# ZombieDelay.net
KiCad netlist of a schematic drawn in EAGLE
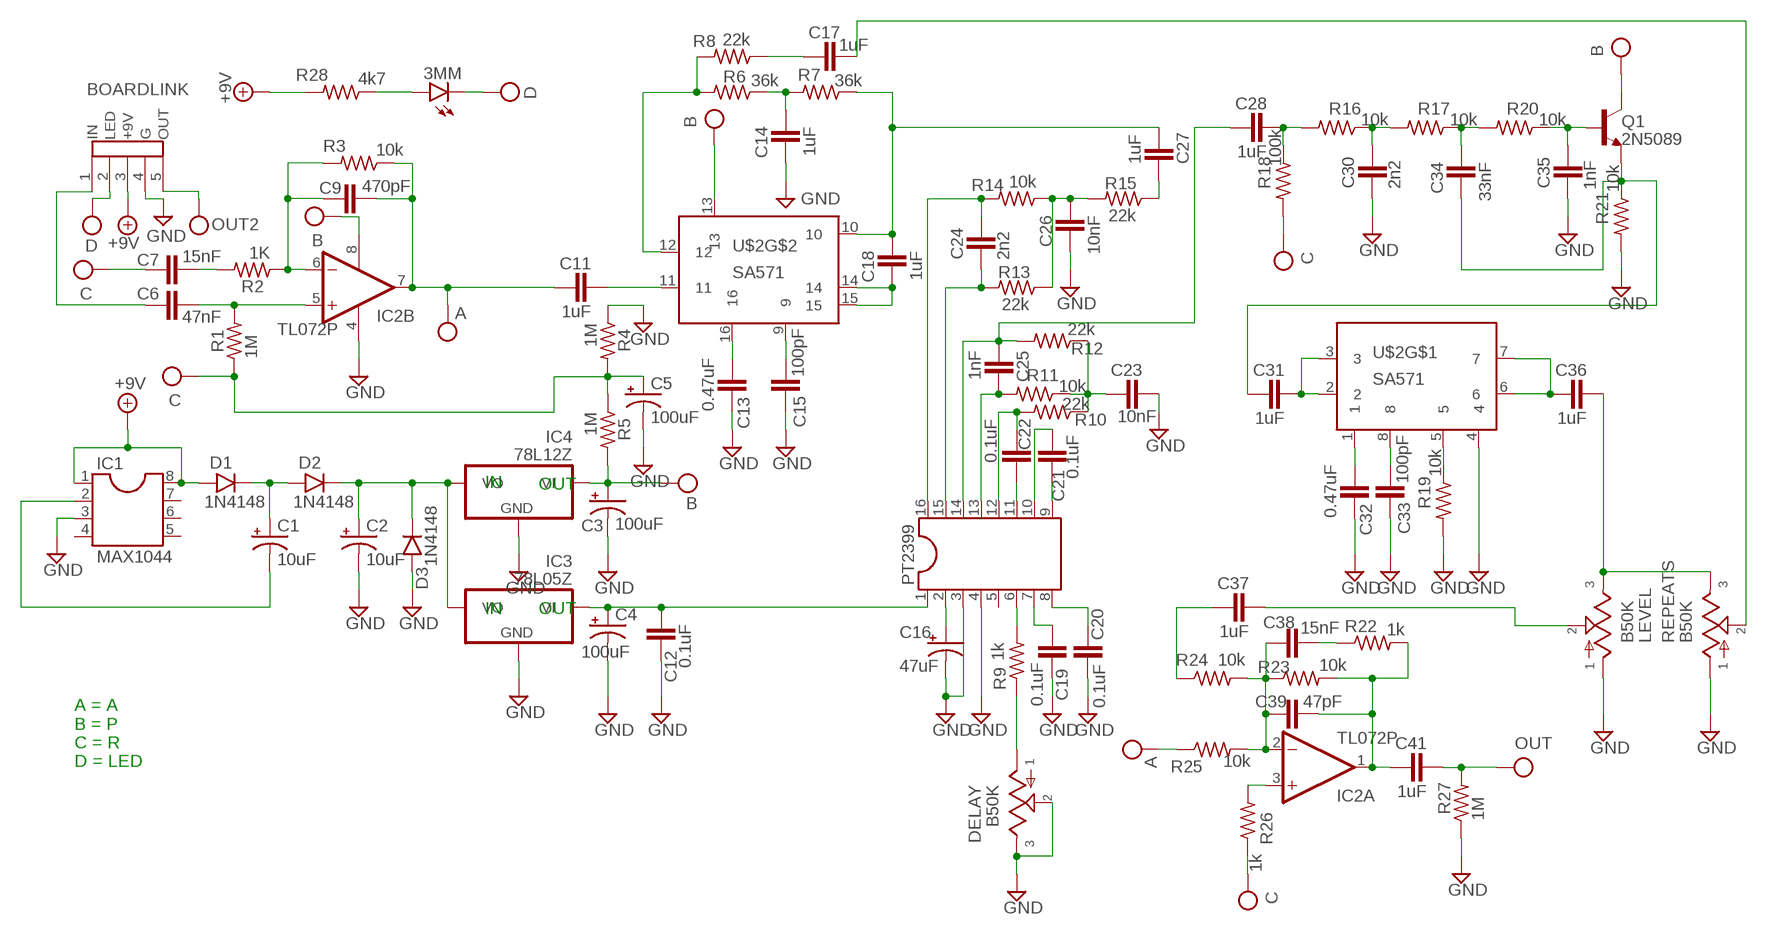
[diagram p0: schematic, sheet 1]

(export (version "E")
  (design (tool "Eeschema 10.0.6"))
  (components
    (comp (ref "3MM")
      (value "LED3MM")
      (footprint "eagle-import:LED3MM")
      (libsource (lib "eagle-import") (part "LED3MM"))
    )
    (comp (ref "C1")
      (value "10uF")
      (footprint "eagle-import:050_020_1")
      (libsource (lib "eagle-import") (part "0501"))
    )
    (comp (ref "C2")
      (value "10uF")
      (footprint "eagle-import:050_020_1")
      (libsource (lib "eagle-import") (part "0501"))
    )
    (comp (ref "C3")
      (value "100uF")
      (footprint "eagle-import:080_035_1")
      (libsource (lib "eagle-import") (part "0801"))
    )
    (comp (ref "C4")
      (value "100uF")
      (footprint "eagle-import:080_035_1")
      (libsource (lib "eagle-import") (part "0801"))
    )
    (comp (ref "C5")
      (value "100uF")
      (footprint "eagle-import:080_035_1")
      (libsource (lib "eagle-import") (part "0801"))
    )
    (comp (ref "C6")
      (value "47nF")
      (footprint "eagle-import:072X035")
      (libsource (lib "eagle-import") (part "072X0352"))
    )
    (comp (ref "C7")
      (value "15nF")
      (footprint "eagle-import:072X025")
      (libsource (lib "eagle-import") (part "072X0252"))
    )
    (comp (ref "C9")
      (value "470pF")
      (footprint "eagle-import:050X030_025")
      (libsource (lib "eagle-import") (part "050X030_0251"))
    )
    (comp (ref "C11")
      (value "1uF")
      (footprint "eagle-import:072X045")
      (libsource (lib "eagle-import") (part "072X0452"))
    )
    (comp (ref "C12")
      (value "0.1uF")
      (footprint "eagle-import:072X035")
      (libsource (lib "eagle-import") (part "072X0352"))
    )
    (comp (ref "C13")
      (value "0.47uF")
      (footprint "eagle-import:072X035")
      (libsource (lib "eagle-import") (part "072X0352"))
    )
    (comp (ref "C14")
      (value "1uF")
      (footprint "eagle-import:072X045")
      (libsource (lib "eagle-import") (part "072X0452"))
    )
    (comp (ref "C15")
      (value "100pF")
      (footprint "eagle-import:050X030_025")
      (libsource (lib "eagle-import") (part "050X030_0251"))
    )
    (comp (ref "C16")
      (value "47uF")
      (footprint "eagle-import:063_025")
      (libsource (lib "eagle-import") (part "0631"))
    )
    (comp (ref "C17")
      (value "1uF")
      (footprint "eagle-import:072X045")
      (libsource (lib "eagle-import") (part "072X0452"))
    )
    (comp (ref "C18")
      (value "1uF")
      (footprint "eagle-import:072X045")
      (libsource (lib "eagle-import") (part "072X0452"))
    )
    (comp (ref "C19")
      (value "0.1uF")
      (footprint "eagle-import:072X035")
      (libsource (lib "eagle-import") (part "072X0352"))
    )
    (comp (ref "C20")
      (value "0.1uF")
      (footprint "eagle-import:072X035")
      (libsource (lib "eagle-import") (part "072X0352"))
    )
    (comp (ref "C21")
      (value "0.1uF")
      (footprint "eagle-import:072X035")
      (libsource (lib "eagle-import") (part "072X0352"))
    )
    (comp (ref "C22")
      (value "0.1uF")
      (footprint "eagle-import:072X035")
      (libsource (lib "eagle-import") (part "072X0352"))
    )
    (comp (ref "C23")
      (value "10nF")
      (footprint "eagle-import:072X025")
      (libsource (lib "eagle-import") (part "072X0252"))
    )
    (comp (ref "C24")
      (value "2n2")
      (footprint "eagle-import:072X025")
      (libsource (lib "eagle-import") (part "072X0252"))
    )
    (comp (ref "C25")
      (value "1nF")
      (footprint "eagle-import:072X025")
      (libsource (lib "eagle-import") (part "072X0252"))
    )
    (comp (ref "C26")
      (value "10nF")
      (footprint "eagle-import:072X025")
      (libsource (lib "eagle-import") (part "072X0252"))
    )
    (comp (ref "C27")
      (value "1uF")
      (footprint "eagle-import:072X045")
      (libsource (lib "eagle-import") (part "072X0452"))
    )
    (comp (ref "C28")
      (value "1uF")
      (footprint "eagle-import:072X045")
      (libsource (lib "eagle-import") (part "072X0452"))
    )
    (comp (ref "C30")
      (value "2n2")
      (footprint "eagle-import:072X025")
      (libsource (lib "eagle-import") (part "072X0252"))
    )
    (comp (ref "C31")
      (value "1uF")
      (footprint "eagle-import:072X045")
      (libsource (lib "eagle-import") (part "072X0452"))
    )
    (comp (ref "C32")
      (value "0.47uF")
      (footprint "eagle-import:072X035")
      (libsource (lib "eagle-import") (part "072X0352"))
    )
    (comp (ref "C33")
      (value "100pF")
      (footprint "eagle-import:050X030_025")
      (libsource (lib "eagle-import") (part "050X030_0251"))
    )
    (comp (ref "C34")
      (value "33nF")
      (footprint "eagle-import:072X025")
      (libsource (lib "eagle-import") (part "072X0252"))
    )
    (comp (ref "C35")
      (value "1nF")
      (footprint "eagle-import:072X025")
      (libsource (lib "eagle-import") (part "072X0252"))
    )
    (comp (ref "C36")
      (value "1uF")
      (footprint "eagle-import:072X045")
      (libsource (lib "eagle-import") (part "072X0452"))
    )
    (comp (ref "C37")
      (value "1uF")
      (footprint "eagle-import:072X045")
      (libsource (lib "eagle-import") (part "072X0452"))
    )
    (comp (ref "C38")
      (value "15nF")
      (footprint "eagle-import:072X025")
      (libsource (lib "eagle-import") (part "072X0252"))
    )
    (comp (ref "C39")
      (value "47pF")
      (footprint "eagle-import:050X030_025")
      (libsource (lib "eagle-import") (part "050X030_0251"))
    )
    (comp (ref "C41")
      (value "1uF")
      (footprint "eagle-import:072X045")
      (libsource (lib "eagle-import") (part "072X0452"))
    )
    (comp (ref "D1")
      (value "1N4148")
      (footprint "eagle-import:DO35-3")
      (libsource (lib "eagle-import") (part "1N4148-3"))
    )
    (comp (ref "D2")
      (value "1N4148")
      (footprint "eagle-import:DO35-3")
      (libsource (lib "eagle-import") (part "1N4148-3"))
    )
    (comp (ref "D3")
      (value "1N4148")
      (footprint "eagle-import:DO35-3")
      (libsource (lib "eagle-import") (part "1N4148-3"))
    )
    (comp (ref "DELAY")
      (value "B50K")
      (footprint "eagle-import:16MM_PCB_PADS")
      (libsource (lib "eagle-import") (part "POT16MM_PCB_PADS"))
    )
    (comp (ref "IC1")
      (value "MAX1044")
      (footprint "eagle-import:DIL08")
      (libsource (lib "eagle-import") (part "MAX1044"))
    )
    (comp (ref "IC2")
      (value "TL072P")
      (footprint "eagle-import:DIL08")
      (libsource (lib "eagle-import") (part "TL072P"))
    )
    (comp (ref "IC3")
      (value "78L05Z")
      (footprint "eagle-import:TO92")
      (libsource (lib "eagle-import") (part "78ZL05"))
    )
    (comp (ref "IC4")
      (value "78L12Z")
      (footprint "eagle-import:TO92")
      (libsource (lib "eagle-import") (part "78ZL12"))
    )
    (comp (ref "LEVEL")
      (value "B50K")
      (footprint "eagle-import:16MM_PCB_PADS")
      (libsource (lib "eagle-import") (part "POT16MM_PCB_PADS"))
    )
    (comp (ref "PT2399")
      (value "DIL16")
      (footprint "eagle-import:DIL16")
      (libsource (lib "eagle-import") (part "DIL16"))
    )
    (comp (ref "Q1")
      (value "2N5089")
      (footprint "eagle-import:TO92-")
      (libsource (lib "eagle-import") (part "2N5089"))
    )
    (comp (ref "R1")
      (value "1M")
      (footprint "eagle-import:R0207_3")
      (libsource (lib "eagle-import") (part "6MM.3"))
    )
    (comp (ref "R2")
      (value "1K")
      (footprint "eagle-import:R0207_3")
      (libsource (lib "eagle-import") (part "6MM.3"))
    )
    (comp (ref "R3")
      (value "10k")
      (footprint "eagle-import:R0207_3")
      (libsource (lib "eagle-import") (part "6MM.3"))
    )
    (comp (ref "R4")
      (value "1M")
      (footprint "eagle-import:R0207_3")
      (libsource (lib "eagle-import") (part "6MM.3"))
    )
    (comp (ref "R5")
      (value "1M")
      (footprint "eagle-import:R0207_3")
      (libsource (lib "eagle-import") (part "6MM.3"))
    )
    (comp (ref "R6")
      (value "36k")
      (footprint "eagle-import:R0207_3")
      (libsource (lib "eagle-import") (part "6MM.3"))
    )
    (comp (ref "R7")
      (value "36k")
      (footprint "eagle-import:R0207_3")
      (libsource (lib "eagle-import") (part "6MM.3"))
    )
    (comp (ref "R8")
      (value "22k")
      (footprint "eagle-import:R0207_3")
      (libsource (lib "eagle-import") (part "6MM.3"))
    )
    (comp (ref "R9")
      (value "1k")
      (footprint "eagle-import:R0207_3")
      (libsource (lib "eagle-import") (part "6MM.3"))
    )
    (comp (ref "R10")
      (value "22k")
      (footprint "eagle-import:R0207_3")
      (libsource (lib "eagle-import") (part "6MM.3"))
    )
    (comp (ref "R11")
      (value "10k")
      (footprint "eagle-import:R0207_3")
      (libsource (lib "eagle-import") (part "6MM.3"))
    )
    (comp (ref "R12")
      (value "22k")
      (footprint "eagle-import:R0207_3")
      (libsource (lib "eagle-import") (part "6MM.3"))
    )
    (comp (ref "R13")
      (value "22k")
      (footprint "eagle-import:R0207_3")
      (libsource (lib "eagle-import") (part "6MM.3"))
    )
    (comp (ref "R14")
      (value "10k")
      (footprint "eagle-import:R0207_3")
      (libsource (lib "eagle-import") (part "6MM.3"))
    )
    (comp (ref "R15")
      (value "22k")
      (footprint "eagle-import:R0207_3")
      (libsource (lib "eagle-import") (part "6MM.3"))
    )
    (comp (ref "R16")
      (value "10k")
      (footprint "eagle-import:R0207_3")
      (libsource (lib "eagle-import") (part "6MM.3"))
    )
    (comp (ref "R17")
      (value "10k")
      (footprint "eagle-import:R0207_3")
      (libsource (lib "eagle-import") (part "6MM.3"))
    )
    (comp (ref "R18")
      (value "100k")
      (footprint "eagle-import:R0207_3")
      (libsource (lib "eagle-import") (part "6MM.3"))
    )
    (comp (ref "R19")
      (value "10k")
      (footprint "eagle-import:R0207_3")
      (libsource (lib "eagle-import") (part "6MM.3"))
    )
    (comp (ref "R20")
      (value "10k")
      (footprint "eagle-import:R0207_3")
      (libsource (lib "eagle-import") (part "6MM.3"))
    )
    (comp (ref "R21")
      (value "10k")
      (footprint "eagle-import:R0207_3")
      (libsource (lib "eagle-import") (part "6MM.3"))
    )
    (comp (ref "R22")
      (value "1k")
      (footprint "eagle-import:R0207_3")
      (libsource (lib "eagle-import") (part "6MM.3"))
    )
    (comp (ref "R23")
      (value "10k")
      (footprint "eagle-import:R0207_3")
      (libsource (lib "eagle-import") (part "6MM.3"))
    )
    (comp (ref "R24")
      (value "10k")
      (footprint "eagle-import:R0207_3")
      (libsource (lib "eagle-import") (part "6MM.3"))
    )
    (comp (ref "R25")
      (value "10k")
      (footprint "eagle-import:R0207_3")
      (libsource (lib "eagle-import") (part "6MM.3"))
    )
    (comp (ref "R26")
      (value "1k")
      (footprint "eagle-import:R0207_3")
      (libsource (lib "eagle-import") (part "6MM.3"))
    )
    (comp (ref "R27")
      (value "1M")
      (footprint "eagle-import:R0207_3")
      (libsource (lib "eagle-import") (part "6MM.3"))
    )
    (comp (ref "R28")
      (value "4k7")
      (footprint "eagle-import:R0207_3")
      (libsource (lib "eagle-import") (part "6MM.3"))
    )
    (comp (ref "REPEATS")
      (value "B50K")
      (footprint "eagle-import:16MM_PCB_PADS")
      (libsource (lib "eagle-import") (part "POT16MM_PCB_PADS"))
    )
    (comp (ref "U$1")
      (value "BOARDLINK")
      (footprint "eagle-import:BOARDLINK")
      (libsource (lib "eagle-import") (part "BOARDLINK"))
    )
    (comp (ref "U$2")
      (value "SA571")
      (footprint "eagle-import:DIL16")
      (libsource (lib "eagle-import") (part "SA571"))
    )
  )
  (nets
    (net (code "1") (name "+9V") (class "Default")
      (node (ref "D1") (pin "A") (pinfunction "A_A") (pintype "passive"))
      (node (ref "IC1") (pin "1") (pinfunction "1_1") (pintype "passive"))
      (node (ref "IC1") (pin "8") (pinfunction "8_8") (pintype "passive"))
      (node (ref "R28") (pin "2") (pinfunction "2_2") (pintype "passive"))
      (node (ref "U$1") (pin "3") (pinfunction "+9V_3") (pintype "bidirectional"))
    )
    (net (code "2") (name "A") (class "Default")
      (node (ref "C11") (pin "1") (pinfunction "1_1") (pintype "passive"))
      (node (ref "C9") (pin "2") (pinfunction "2_2") (pintype "passive"))
      (node (ref "IC2") (pin "7") (pinfunction "OUT_7") (pintype "output"))
      (node (ref "R25") (pin "1") (pinfunction "1_1") (pintype "passive"))
      (node (ref "R3") (pin "1") (pinfunction "1_1") (pintype "passive"))
    )
    (net (code "3") (name "B") (class "Default")
      (node (ref "C3") (pin "+") (pinfunction "+_+") (pintype "passive"))
      (node (ref "IC2") (pin "8") (pinfunction "V+_8") (pintype "power_in"))
      (node (ref "IC4") (pin "1") (pinfunction "VI_1") (pintype "input"))
      (node (ref "Q1") (pin "1") (pinfunction "C_1") (pintype "passive"))
      (node (ref "R5") (pin "2") (pinfunction "2_2") (pintype "passive"))
      (node (ref "U$2") (pin "13") (pinfunction "13_13") (pintype "bidirectional"))
    )
    (net (code "4") (name "C") (class "Default")
      (node (ref "C5") (pin "+") (pinfunction "+_+") (pintype "passive"))
      (node (ref "C7") (pin "1") (pinfunction "1_1") (pintype "passive"))
      (node (ref "R1") (pin "1") (pinfunction "1_1") (pintype "passive"))
      (node (ref "R18") (pin "2") (pinfunction "2_2") (pintype "passive"))
      (node (ref "R26") (pin "1") (pinfunction "1_1") (pintype "passive"))
      (node (ref "R4") (pin "2") (pinfunction "2_2") (pintype "passive"))
      (node (ref "R5") (pin "1") (pinfunction "1_1") (pintype "passive"))
    )
    (net (code "5") (name "D") (class "Default")
      (node (ref "3MM") (pin "K") (pinfunction "C_K") (pintype "passive"))
      (node (ref "U$1") (pin "2") (pinfunction "LED_2") (pintype "bidirectional"))
    )
    (net (code "6") (name "GND") (class "Default")
      (node (ref "C12") (pin "1") (pinfunction "1_1") (pintype "passive"))
      (node (ref "C13") (pin "2") (pinfunction "2_2") (pintype "passive"))
      (node (ref "C14") (pin "1") (pinfunction "1_1") (pintype "passive"))
      (node (ref "C15") (pin "1") (pinfunction "1_1") (pintype "passive"))
      (node (ref "C16") (pin "-") (pinfunction "-_-") (pintype "passive"))
      (node (ref "C19") (pin "2") (pinfunction "2_2") (pintype "passive"))
      (node (ref "C2") (pin "-") (pinfunction "-_-") (pintype "passive"))
      (node (ref "C20") (pin "2") (pinfunction "2_2") (pintype "passive"))
      (node (ref "C23") (pin "2") (pinfunction "2_2") (pintype "passive"))
      (node (ref "C26") (pin "1") (pinfunction "1_1") (pintype "passive"))
      (node (ref "C3") (pin "-") (pinfunction "-_-") (pintype "passive"))
      (node (ref "C30") (pin "1") (pinfunction "1_1") (pintype "passive"))
      (node (ref "C32") (pin "2") (pinfunction "2_2") (pintype "passive"))
      (node (ref "C33") (pin "1") (pinfunction "1_1") (pintype "passive"))
      (node (ref "C35") (pin "1") (pinfunction "1_1") (pintype "passive"))
      (node (ref "C4") (pin "-") (pinfunction "-_-") (pintype "passive"))
      (node (ref "C5") (pin "-") (pinfunction "-_-") (pintype "passive"))
      (node (ref "D3") (pin "A") (pinfunction "A_A") (pintype "passive"))
      (node (ref "DELAY") (pin "2") (pinfunction "2_2") (pintype "passive"))
      (node (ref "DELAY") (pin "3") (pinfunction "3_3") (pintype "passive"))
      (node (ref "IC1") (pin "3") (pinfunction "3_3") (pintype "passive"))
      (node (ref "IC2") (pin "4") (pinfunction "V-_4") (pintype "power_in"))
      (node (ref "IC3") (pin "2") (pinfunction "GND_2") (pintype "passive"))
      (node (ref "IC4") (pin "2") (pinfunction "GND_2") (pintype "passive"))
      (node (ref "LEVEL") (pin "1") (pinfunction "1_1") (pintype "passive"))
      (node (ref "PT2399") (pin "3") (pinfunction "3_3") (pintype "passive"))
      (node (ref "PT2399") (pin "4") (pinfunction "4_4") (pintype "passive"))
      (node (ref "R19") (pin "2") (pinfunction "2_2") (pintype "passive"))
      (node (ref "R21") (pin "2") (pinfunction "2_2") (pintype "passive"))
      (node (ref "R27") (pin "1") (pinfunction "1_1") (pintype "passive"))
      (node (ref "R4") (pin "1") (pinfunction "1_1") (pintype "passive"))
      (node (ref "REPEATS") (pin "1") (pinfunction "1_1") (pintype "passive"))
      (node (ref "U$1") (pin "4") (pinfunction "G_4") (pintype "bidirectional"))
      (node (ref "U$2") (pin "4") (pinfunction "4_4") (pintype "bidirectional"))
    )
    (net (code "7") (name "Net-(3MM-PadA)") (class "Default")
      (node (ref "3MM") (pin "A") (pinfunction "A_A") (pintype "passive"))
      (node (ref "R28") (pin "1") (pinfunction "1_1") (pintype "passive"))
    )
    (net (code "8") (name "Net-(C1-Pad+)") (class "Default")
      (node (ref "C1") (pin "+") (pinfunction "+_+") (pintype "passive"))
      (node (ref "D1") (pin "C") (pinfunction "C_C") (pintype "passive"))
      (node (ref "D2") (pin "A") (pinfunction "A_A") (pintype "passive"))
    )
    (net (code "9") (name "Net-(C1-Pad-)") (class "Default")
      (node (ref "C1") (pin "-") (pinfunction "-_-") (pintype "passive"))
      (node (ref "IC1") (pin "2") (pinfunction "2_2") (pintype "passive"))
    )
    (net (code "10") (name "Net-(C7-Pad2)") (class "Default")
      (node (ref "C7") (pin "2") (pinfunction "2_2") (pintype "passive"))
      (node (ref "R2") (pin "2") (pinfunction "2_2") (pintype "passive"))
    )
    (net (code "11") (name "Net-(C11-Pad2)") (class "Default")
      (node (ref "C11") (pin "2") (pinfunction "2_2") (pintype "passive"))
      (node (ref "U$2") (pin "11") (pinfunction "11_11") (pintype "bidirectional"))
    )
    (net (code "12") (name "Net-(C13-Pad1)") (class "Default")
      (node (ref "C13") (pin "1") (pinfunction "1_1") (pintype "passive"))
      (node (ref "U$2") (pin "16") (pinfunction "16_16") (pintype "bidirectional"))
    )
    (net (code "13") (name "Net-(C14-Pad2)") (class "Default")
      (node (ref "C14") (pin "2") (pinfunction "2_2") (pintype "passive"))
      (node (ref "R6") (pin "1") (pinfunction "1_1") (pintype "passive"))
      (node (ref "R7") (pin "2") (pinfunction "2_2") (pintype "passive"))
    )
    (net (code "14") (name "Net-(C15-Pad2)") (class "Default")
      (node (ref "C15") (pin "2") (pinfunction "2_2") (pintype "passive"))
      (node (ref "U$2") (pin "9") (pinfunction "9_9") (pintype "bidirectional"))
    )
    (net (code "15") (name "Net-(C16-Pad+)") (class "Default")
      (node (ref "C16") (pin "+") (pinfunction "+_+") (pintype "passive"))
      (node (ref "PT2399") (pin "2") (pinfunction "2_2") (pintype "passive"))
    )
    (net (code "16") (name "Net-(C17-Pad1)") (class "Default")
      (node (ref "C17") (pin "1") (pinfunction "1_1") (pintype "passive"))
      (node (ref "R8") (pin "1") (pinfunction "1_1") (pintype "passive"))
    )
    (net (code "17") (name "Net-(C17-Pad2)") (class "Default")
      (node (ref "C17") (pin "2") (pinfunction "2_2") (pintype "passive"))
      (node (ref "REPEATS") (pin "2") (pinfunction "2_2") (pintype "passive"))
    )
    (net (code "18") (name "Net-(C18-Pad1)") (class "Default")
      (node (ref "C18") (pin "1") (pinfunction "1_1") (pintype "passive"))
      (node (ref "U$2") (pin "14") (pinfunction "14_14") (pintype "bidirectional"))
      (node (ref "U$2") (pin "15") (pinfunction "15_15") (pintype "bidirectional"))
    )
    (net (code "19") (name "Net-(C18-Pad2)") (class "Default")
      (node (ref "C18") (pin "2") (pinfunction "2_2") (pintype "passive"))
      (node (ref "C27") (pin "1") (pinfunction "1_1") (pintype "passive"))
      (node (ref "R7") (pin "1") (pinfunction "1_1") (pintype "passive"))
      (node (ref "U$2") (pin "10") (pinfunction "10_10") (pintype "bidirectional"))
    )
    (net (code "20") (name "Net-(C19-Pad1)") (class "Default")
      (node (ref "C19") (pin "1") (pinfunction "1_1") (pintype "passive"))
      (node (ref "PT2399") (pin "7") (pinfunction "7_7") (pintype "passive"))
    )
    (net (code "21") (name "Net-(C20-Pad1)") (class "Default")
      (node (ref "C20") (pin "1") (pinfunction "1_1") (pintype "passive"))
      (node (ref "PT2399") (pin "8") (pinfunction "8_8") (pintype "passive"))
    )
    (net (code "22") (name "Net-(C21-Pad1)") (class "Default")
      (node (ref "C21") (pin "1") (pinfunction "1_1") (pintype "passive"))
      (node (ref "PT2399") (pin "10") (pinfunction "10_10") (pintype "passive"))
    )
    (net (code "23") (name "Net-(C21-Pad2)") (class "Default")
      (node (ref "C21") (pin "2") (pinfunction "2_2") (pintype "passive"))
      (node (ref "PT2399") (pin "9") (pinfunction "9_9") (pintype "passive"))
    )
    (net (code "24") (name "Net-(C22-Pad1)") (class "Default")
      (node (ref "C22") (pin "1") (pinfunction "1_1") (pintype "passive"))
      (node (ref "PT2399") (pin "12") (pinfunction "12_12") (pintype "passive"))
      (node (ref "R10") (pin "2") (pinfunction "2_2") (pintype "passive"))
    )
    (net (code "25") (name "Net-(C22-Pad2)") (class "Default")
      (node (ref "C22") (pin "2") (pinfunction "2_2") (pintype "passive"))
      (node (ref "PT2399") (pin "11") (pinfunction "11_11") (pintype "passive"))
    )
    (net (code "26") (name "Net-(C23-Pad1)") (class "Default")
      (node (ref "C23") (pin "1") (pinfunction "1_1") (pintype "passive"))
      (node (ref "R10") (pin "1") (pinfunction "1_1") (pintype "passive"))
      (node (ref "R11") (pin "1") (pinfunction "1_1") (pintype "passive"))
      (node (ref "R12") (pin "1") (pinfunction "1_1") (pintype "passive"))
    )
    (net (code "27") (name "Net-(C24-Pad1)") (class "Default")
      (node (ref "C24") (pin "1") (pinfunction "1_1") (pintype "passive"))
      (node (ref "PT2399") (pin "15") (pinfunction "15_15") (pintype "passive"))
      (node (ref "R13") (pin "2") (pinfunction "2_2") (pintype "passive"))
    )
    (net (code "28") (name "Net-(C24-Pad2)") (class "Default")
      (node (ref "C24") (pin "2") (pinfunction "2_2") (pintype "passive"))
      (node (ref "PT2399") (pin "16") (pinfunction "16_16") (pintype "passive"))
      (node (ref "R14") (pin "2") (pinfunction "2_2") (pintype "passive"))
    )
    (net (code "29") (name "Net-(C25-Pad1)") (class "Default")
      (node (ref "C25") (pin "1") (pinfunction "1_1") (pintype "passive"))
      (node (ref "PT2399") (pin "13") (pinfunction "13_13") (pintype "passive"))
      (node (ref "R11") (pin "2") (pinfunction "2_2") (pintype "passive"))
    )
    (net (code "30") (name "Net-(C25-Pad2)") (class "Default")
      (node (ref "C25") (pin "2") (pinfunction "2_2") (pintype "passive"))
      (node (ref "C28") (pin "1") (pinfunction "1_1") (pintype "passive"))
      (node (ref "PT2399") (pin "14") (pinfunction "14_14") (pintype "passive"))
      (node (ref "R12") (pin "2") (pinfunction "2_2") (pintype "passive"))
    )
    (net (code "31") (name "Net-(C26-Pad2)") (class "Default")
      (node (ref "C26") (pin "2") (pinfunction "2_2") (pintype "passive"))
      (node (ref "R13") (pin "1") (pinfunction "1_1") (pintype "passive"))
      (node (ref "R14") (pin "1") (pinfunction "1_1") (pintype "passive"))
      (node (ref "R15") (pin "2") (pinfunction "2_2") (pintype "passive"))
    )
    (net (code "32") (name "Net-(C27-Pad2)") (class "Default")
      (node (ref "C27") (pin "2") (pinfunction "2_2") (pintype "passive"))
      (node (ref "R15") (pin "1") (pinfunction "1_1") (pintype "passive"))
    )
    (net (code "33") (name "Net-(C28-Pad2)") (class "Default")
      (node (ref "C28") (pin "2") (pinfunction "2_2") (pintype "passive"))
      (node (ref "R16") (pin "2") (pinfunction "2_2") (pintype "passive"))
      (node (ref "R18") (pin "1") (pinfunction "1_1") (pintype "passive"))
    )
    (net (code "34") (name "Net-(C30-Pad2)") (class "Default")
      (node (ref "C30") (pin "2") (pinfunction "2_2") (pintype "passive"))
      (node (ref "R16") (pin "1") (pinfunction "1_1") (pintype "passive"))
      (node (ref "R17") (pin "2") (pinfunction "2_2") (pintype "passive"))
    )
    (net (code "35") (name "Net-(C31-Pad2)") (class "Default")
      (node (ref "C31") (pin "2") (pinfunction "2_2") (pintype "passive"))
      (node (ref "U$2") (pin "2") (pinfunction "2_2") (pintype "bidirectional"))
      (node (ref "U$2") (pin "3") (pinfunction "3_3") (pintype "bidirectional"))
    )
    (net (code "36") (name "Net-(C32-Pad1)") (class "Default")
      (node (ref "C32") (pin "1") (pinfunction "1_1") (pintype "passive"))
      (node (ref "U$2") (pin "1") (pinfunction "1_1") (pintype "bidirectional"))
    )
    (net (code "37") (name "Net-(C33-Pad2)") (class "Default")
      (node (ref "C33") (pin "2") (pinfunction "2_2") (pintype "passive"))
      (node (ref "U$2") (pin "8") (pinfunction "8_8") (pintype "bidirectional"))
    )
    (net (code "38") (name "Net-(C34-Pad2)") (class "Default")
      (node (ref "C34") (pin "2") (pinfunction "2_2") (pintype "passive"))
      (node (ref "R17") (pin "1") (pinfunction "1_1") (pintype "passive"))
      (node (ref "R20") (pin "2") (pinfunction "2_2") (pintype "passive"))
    )
    (net (code "39") (name "Net-(C36-Pad1)") (class "Default")
      (node (ref "C36") (pin "1") (pinfunction "1_1") (pintype "passive"))
      (node (ref "U$2") (pin "6") (pinfunction "6_6") (pintype "bidirectional"))
      (node (ref "U$2") (pin "7") (pinfunction "7_7") (pintype "bidirectional"))
    )
    (net (code "40") (name "Net-(C36-Pad2)") (class "Default")
      (node (ref "C36") (pin "2") (pinfunction "2_2") (pintype "passive"))
      (node (ref "LEVEL") (pin "3") (pinfunction "3_3") (pintype "passive"))
      (node (ref "REPEATS") (pin "3") (pinfunction "3_3") (pintype "passive"))
    )
    (net (code "41") (name "Net-(C37-Pad1)") (class "Default")
      (node (ref "C37") (pin "1") (pinfunction "1_1") (pintype "passive"))
      (node (ref "R24") (pin "1") (pinfunction "1_1") (pintype "passive"))
    )
    (net (code "42") (name "Net-(C37-Pad2)") (class "Default")
      (node (ref "C37") (pin "2") (pinfunction "2_2") (pintype "passive"))
      (node (ref "LEVEL") (pin "2") (pinfunction "2_2") (pintype "passive"))
    )
    (net (code "43") (name "Net-(C38-Pad1)") (class "Default")
      (node (ref "C38") (pin "1") (pinfunction "1_1") (pintype "passive"))
      (node (ref "R22") (pin "1") (pinfunction "1_1") (pintype "passive"))
    )
    (net (code "44") (name "Net-(DELAY-Pad1)") (class "Default")
      (node (ref "DELAY") (pin "1") (pinfunction "1_1") (pintype "passive"))
      (node (ref "R9") (pin "1") (pinfunction "1_1") (pintype "passive"))
    )
    (net (code "45") (name "Net-(IC2A-+IN)") (class "Default")
      (node (ref "IC2") (pin "3") (pinfunction "+IN_3") (pintype "input"))
      (node (ref "R26") (pin "2") (pinfunction "2_2") (pintype "passive"))
    )
    (net (code "46") (name "Net-(IC2A--IN)") (class "Default")
      (node (ref "C38") (pin "2") (pinfunction "2_2") (pintype "passive"))
      (node (ref "C39") (pin "2") (pinfunction "2_2") (pintype "passive"))
      (node (ref "IC2") (pin "2") (pinfunction "-IN_2") (pintype "input"))
      (node (ref "R23") (pin "1") (pinfunction "1_1") (pintype "passive"))
      (node (ref "R24") (pin "2") (pinfunction "2_2") (pintype "passive"))
      (node (ref "R25") (pin "2") (pinfunction "2_2") (pintype "passive"))
    )
    (net (code "47") (name "Net-(IC2A-OUT)") (class "Default")
      (node (ref "C39") (pin "1") (pinfunction "1_1") (pintype "passive"))
      (node (ref "C41") (pin "1") (pinfunction "1_1") (pintype "passive"))
      (node (ref "IC2") (pin "1") (pinfunction "OUT_1") (pintype "output"))
      (node (ref "R22") (pin "2") (pinfunction "2_2") (pintype "passive"))
      (node (ref "R23") (pin "2") (pinfunction "2_2") (pintype "passive"))
    )
    (net (code "48") (name "Net-(IC2B-+IN)") (class "Default")
      (node (ref "C6") (pin "2") (pinfunction "2_2") (pintype "passive"))
      (node (ref "IC2") (pin "5") (pinfunction "+IN_5") (pintype "input"))
      (node (ref "R1") (pin "2") (pinfunction "2_2") (pintype "passive"))
    )
    (net (code "49") (name "Net-(IC2B--IN)") (class "Default")
      (node (ref "C9") (pin "1") (pinfunction "1_1") (pintype "passive"))
      (node (ref "IC2") (pin "6") (pinfunction "-IN_6") (pintype "input"))
      (node (ref "R2") (pin "1") (pinfunction "1_1") (pintype "passive"))
      (node (ref "R3") (pin "2") (pinfunction "2_2") (pintype "passive"))
    )
    (net (code "50") (name "Net-(IC3-VI)") (class "Default")
      (node (ref "C12") (pin "2") (pinfunction "2_2") (pintype "passive"))
      (node (ref "C4") (pin "+") (pinfunction "+_+") (pintype "passive"))
      (node (ref "IC3") (pin "1") (pinfunction "VI_1") (pintype "input"))
      (node (ref "PT2399") (pin "1") (pinfunction "1_1") (pintype "passive"))
    )
    (net (code "51") (name "Net-(IC3-VO)") (class "Default")
      (node (ref "C2") (pin "+") (pinfunction "+_+") (pintype "passive"))
      (node (ref "D2") (pin "C") (pinfunction "C_C") (pintype "passive"))
      (node (ref "D3") (pin "C") (pinfunction "C_C") (pintype "passive"))
      (node (ref "IC3") (pin "3") (pinfunction "VO_3") (pintype "passive"))
      (node (ref "IC4") (pin "3") (pinfunction "VO_3") (pintype "passive"))
    )
    (net (code "52") (name "Net-(PT2399-Pad6)") (class "Default")
      (node (ref "PT2399") (pin "6") (pinfunction "6_6") (pintype "passive"))
      (node (ref "R9") (pin "2") (pinfunction "2_2") (pintype "passive"))
    )
    (net (code "53") (name "Net-(Q1-B)") (class "Default")
      (node (ref "C35") (pin "2") (pinfunction "2_2") (pintype "passive"))
      (node (ref "Q1") (pin "2") (pinfunction "B_2") (pintype "passive"))
      (node (ref "R20") (pin "1") (pinfunction "1_1") (pintype "passive"))
    )
    (net (code "54") (name "Net-(Q1-E)") (class "Default")
      (node (ref "C31") (pin "1") (pinfunction "1_1") (pintype "passive"))
      (node (ref "C34") (pin "1") (pinfunction "1_1") (pintype "passive"))
      (node (ref "Q1") (pin "3") (pinfunction "E_3") (pintype "passive"))
      (node (ref "R21") (pin "1") (pinfunction "1_1") (pintype "passive"))
    )
    (net (code "55") (name "Net-(R6-Pad2)") (class "Default")
      (node (ref "R6") (pin "2") (pinfunction "2_2") (pintype "passive"))
      (node (ref "R8") (pin "2") (pinfunction "2_2") (pintype "passive"))
      (node (ref "U$2") (pin "12") (pinfunction "12_12") (pintype "bidirectional"))
    )
    (net (code "56") (name "Net-(R19-Pad1)") (class "Default")
      (node (ref "R19") (pin "1") (pinfunction "1_1") (pintype "passive"))
      (node (ref "U$2") (pin "5") (pinfunction "5_5") (pintype "bidirectional"))
    )
    (net (code "57") (name "Net-(U$1-IN)") (class "Default")
      (node (ref "C6") (pin "1") (pinfunction "1_1") (pintype "passive"))
      (node (ref "U$1") (pin "1") (pinfunction "IN_1") (pintype "bidirectional"))
    )
    (net (code "58") (name "OUT") (class "Default")
      (node (ref "C41") (pin "2") (pinfunction "2_2") (pintype "passive"))
      (node (ref "R27") (pin "2") (pinfunction "2_2") (pintype "passive"))
      (node (ref "U$1") (pin "5") (pinfunction "OUT_5") (pintype "bidirectional"))
    )
    (net (code "59") (name "unconnected-(IC1-Pad4)") (class "Default")
      (node (ref "IC1") (pin "4") (pinfunction "4_4") (pintype "passive"))
    )
    (net (code "60") (name "unconnected-(IC1-Pad5)") (class "Default")
      (node (ref "IC1") (pin "5") (pinfunction "5_5") (pintype "passive"))
    )
    (net (code "61") (name "unconnected-(IC1-Pad6)") (class "Default")
      (node (ref "IC1") (pin "6") (pinfunction "6_6") (pintype "passive"))
    )
    (net (code "62") (name "unconnected-(IC1-Pad7)") (class "Default")
      (node (ref "IC1") (pin "7") (pinfunction "7_7") (pintype "passive"))
    )
    (net (code "63") (name "unconnected-(PT2399-Pad5)") (class "Default")
      (node (ref "PT2399") (pin "5") (pinfunction "5_5") (pintype "passive"))
    )
  )
)
